# Power_Supply_Alternate.net
KiCad netlist of a schematic drawn in Altium Designer
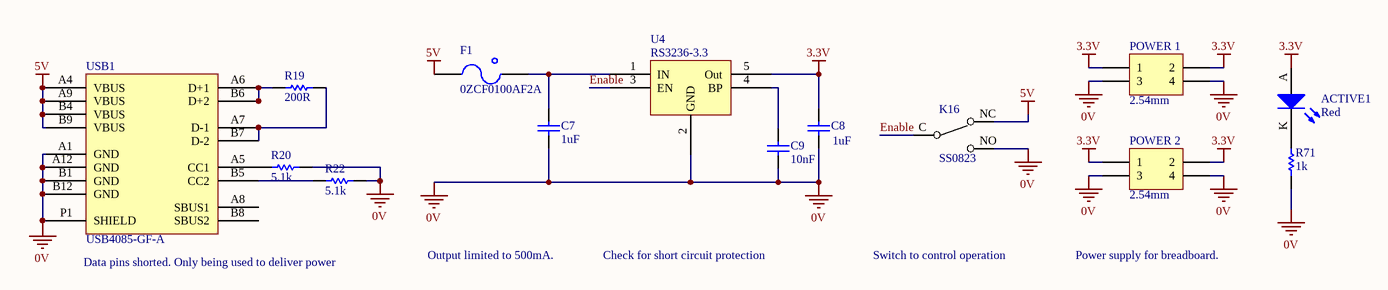
[diagram p0: Power Supply (Alternate).SchDoc]

(export (version "E")
  (design (tool "Eeschema 10.0.6"))
  (components
    (comp (ref "ACTIVE1")
      (value "Red")
      (footprint "0805 LED")
      (description "Red LED Indication - Discrete 1.75V 0805 (2012 Metric)")
      (fields (field (name "PART NUMBER") "SML-210LTT86") (field (name "MANUFACTURER") "ROHM Semiconductor"))
      (libsource (lib "ts_19-standard-library") (part "LED"))
    )
    (comp (ref "C7")
      (value "1uF")
      (footprint "0805")
      (fields
        (field (name "PART NUMBER") "GCM21BR71A105KA37L")
        (field (name "TOLERANCE") "10%")
        (field (name "MANUFACTURER") "muRata")
      )
      (libsource (lib "ts_19-standard-library") (part "Capacitor"))
    )
    (comp (ref "C8")
      (value "1uF")
      (footprint "0805")
      (fields
        (field (name "PART NUMBER") "GCM21BR71A105KA37L")
        (field (name "TOLERANCE") "10%")
        (field (name "MANUFACTURER") "muRata")
      )
      (libsource (lib "ts_19-standard-library") (part "Capacitor"))
    )
    (comp (ref "C9")
      (value "10nF")
      (footprint "0805")
      (fields
        (field (name "PART NUMBER") "GCM21BR71H103KA37L")
        (field (name "TOLERANCE") "10%")
        (field (name "MANUFACTURER") "muRata")
      )
      (libsource (lib "ts_19-standard-library") (part "Capacitor"))
    )
    (comp (ref "F1")
      (value "0ZCF0100AF2A")
      (footprint "2920")
      (description "PTC RESET FUSE 60V 1A 292")
      (fields
        (field (name "MANUFACTURER") "Littelfuse Inc.")
        (field (name "DIGIKEY PART NUMBER") "507-2070-1-ND")
      )
      (libsource (lib "ts_19-standard-library") (part "PTC Fuse"))
    )
    (comp (ref "K16")
      (value "SS0823")
      (footprint "Jaycar 2.54 SPDT Slide")
      (description "SPDT Switch")
      (fields (field (name "MANUFACTURER") "Jaycar"))
      (libsource (lib "ts_19-standard-library") (part "SPDT"))
    )
    (comp (ref "POWER 1")
      (value "2.54mm")
      (footprint "Header 2x2")
      (fields (field (name "PART NUMBER") "Header 2x2") (field (name "CONTACT") "NA"))
      (libsource (lib "ts_19-standard-connectors-IED") (part "Header 2x2"))
    )
    (comp (ref "POWER 2")
      (value "2.54mm")
      (footprint "Header 2x2")
      (fields (field (name "PART NUMBER") "Header 2x2") (field (name "CONTACT") "NA"))
      (libsource (lib "ts_19-standard-connectors-IED") (part "Header 2x2"))
    )
    (comp (ref "R19")
      (value "200R")
      (footprint "0805")
      (fields
        (field (name "MANUFACTURER") "YAGEO")
        (field (name "PART NUMBER") "RC0805FR07200RL")
        (field (name "TOLERANCE") "0.01")
      )
      (libsource (lib "ts_19-standard-library-IED") (part "Resistor"))
    )
    (comp (ref "R20")
      (value "5.1k")
      (footprint "0805")
      (fields
        (field (name "MANUFACTURER") "YAGEO")
        (field (name "PART NUMBER") "RC0805FR075K1L")
        (field (name "TOLERANCE") "0.01")
      )
      (libsource (lib "ts_19-standard-library-IED") (part "Resistor"))
    )
    (comp (ref "R22")
      (value "5.1k")
      (footprint "0805")
      (fields
        (field (name "MANUFACTURER") "YAGEO")
        (field (name "PART NUMBER") "RC0805FR075K1L")
        (field (name "TOLERANCE") "0.01")
      )
      (libsource (lib "ts_19-standard-library-IED") (part "Resistor"))
    )
    (comp (ref "R71")
      (value "1k")
      (footprint "0805")
      (fields
        (field (name "PART NUMBER") "RC0805FR071KL")
        (field (name "MANUFACTURER") "YAGEO")
        (field (name "TOLERANCE") "0.01")
      )
      (libsource (lib "ts_19-standard-library") (part "Resistor"))
    )
    (comp (ref "U4")
      (value "RS3236-3.3")
      (footprint "Runic SOT-23-5")
      (description "Low Power, Low Dropout, 500mA RF LinearRegulators")
      (fields (field (name "MANUFACTURER") "RUNIC"))
      (libsource (lib "ts_19-standard-library") (part "RS3236-3.3"))
    )
    (comp (ref "USB1")
      (value "USB4085-GF-A")
      (footprint "USB4085-GF-A")
      (description "USB - C (Type - C) USB 2.0 Receptacle Connector 16 Position Through Hole, Right Angle")
      (fields (field (name "DIGIKEY PART NUMBER") "2073-USB4085-GF-ACT-ND"))
      (libsource (lib "ts_19-standard-connectors") (part "USB4085-GF-A"))
    )
  )
  (nets
    (net (code "1") (name "/Enable") (class "Default")
      (node (ref "K16") (pin "C") (pinfunction "C_C") (pintype "passive"))
      (node (ref "U4") (pin "3") (pinfunction "EN_3") (pintype "passive"))
    )
    (net (code "2") (name "0V") (class "Default")
      (node (ref "C7") (pin "1") (pinfunction "1_1") (pintype "passive"))
      (node (ref "C8") (pin "1") (pinfunction "1_1") (pintype "passive"))
      (node (ref "C9") (pin "1") (pinfunction "1_1") (pintype "passive"))
      (node (ref "K16") (pin "NO") (pinfunction "NO_NO") (pintype "passive"))
      (node (ref "POWER 1") (pin "3") (pinfunction "3_3") (pintype "passive"))
      (node (ref "POWER 1") (pin "4") (pinfunction "4_4") (pintype "passive"))
      (node (ref "POWER 2") (pin "3") (pinfunction "3_3") (pintype "passive"))
      (node (ref "POWER 2") (pin "4") (pinfunction "4_4") (pintype "passive"))
      (node (ref "R20") (pin "2") (pinfunction "2_2") (pintype "passive"))
      (node (ref "R22") (pin "2") (pinfunction "2_2") (pintype "passive"))
      (node (ref "R71") (pin "1") (pinfunction "1_1") (pintype "passive"))
      (node (ref "U4") (pin "2") (pinfunction "GND_2") (pintype "passive"))
      (node (ref "USB1") (pin "A1") (pinfunction "GND_A1") (pintype "passive"))
      (node (ref "USB1") (pin "A12") (pinfunction "GND_A12") (pintype "passive"))
      (node (ref "USB1") (pin "B1") (pinfunction "GND_B1") (pintype "passive"))
      (node (ref "USB1") (pin "B12") (pinfunction "GND_B12") (pintype "passive"))
      (node (ref "USB1") (pin "P1") (pinfunction "SHIELD_P1") (pintype "passive"))
    )
    (net (code "3") (name "3.3V") (class "Default")
      (node (ref "ACTIVE1") (pin "A") (pinfunction "A_A") (pintype "passive"))
      (node (ref "C8") (pin "2") (pinfunction "2_2") (pintype "passive"))
      (node (ref "POWER 1") (pin "1") (pinfunction "1_1") (pintype "passive"))
      (node (ref "POWER 1") (pin "2") (pinfunction "2_2") (pintype "passive"))
      (node (ref "POWER 2") (pin "1") (pinfunction "1_1") (pintype "passive"))
      (node (ref "POWER 2") (pin "2") (pinfunction "2_2") (pintype "passive"))
      (node (ref "U4") (pin "5") (pinfunction "Out_5") (pintype "passive"))
    )
    (net (code "4") (name "5V") (class "Default")
      (node (ref "F1") (pin "1") (pinfunction "1_1") (pintype "passive"))
      (node (ref "K16") (pin "NC") (pinfunction "NC_NC") (pintype "passive"))
      (node (ref "USB1") (pin "A4") (pinfunction "VBUS_A4") (pintype "passive"))
      (node (ref "USB1") (pin "A9") (pinfunction "VBUS_A9") (pintype "passive"))
      (node (ref "USB1") (pin "B4") (pinfunction "VBUS_B4") (pintype "passive"))
      (node (ref "USB1") (pin "B9") (pinfunction "VBUS_B9") (pintype "passive"))
    )
    (net (code "5") (name "Net-(ACTIVE1-PadK)") (class "Default")
      (node (ref "ACTIVE1") (pin "K") (pinfunction "K_K") (pintype "passive"))
      (node (ref "R71") (pin "2") (pinfunction "2_2") (pintype "passive"))
    )
    (net (code "6") (name "Net-(U4-BP)") (class "Default")
      (node (ref "C9") (pin "2") (pinfunction "2_2") (pintype "passive"))
      (node (ref "U4") (pin "4") (pinfunction "BP_4") (pintype "passive"))
    )
    (net (code "7") (name "Net-(U4-IN)") (class "Default")
      (node (ref "C7") (pin "2") (pinfunction "2_2") (pintype "passive"))
      (node (ref "F1") (pin "2") (pinfunction "2_2") (pintype "passive"))
      (node (ref "U4") (pin "1") (pinfunction "IN_1") (pintype "passive"))
    )
    (net (code "8") (name "Net-(USB1-CC1)") (class "Default")
      (node (ref "R20") (pin "1") (pinfunction "1_1") (pintype "passive"))
      (node (ref "USB1") (pin "A5") (pinfunction "CC1_A5") (pintype "passive"))
    )
    (net (code "9") (name "Net-(USB1-CC2)") (class "Default")
      (node (ref "R22") (pin "1") (pinfunction "1_1") (pintype "passive"))
      (node (ref "USB1") (pin "B5") (pinfunction "CC2_B5") (pintype "passive"))
    )
    (net (code "10") (name "Net-(USB1-D+1)") (class "Default")
      (node (ref "R19") (pin "1") (pinfunction "1_1") (pintype "passive"))
      (node (ref "USB1") (pin "A6") (pinfunction "D+1_A6") (pintype "passive"))
      (node (ref "USB1") (pin "B6") (pinfunction "D+2_B6") (pintype "passive"))
    )
    (net (code "11") (name "Net-(USB1-D-1)") (class "Default")
      (node (ref "R19") (pin "2") (pinfunction "2_2") (pintype "passive"))
      (node (ref "USB1") (pin "A7") (pinfunction "D-1_A7") (pintype "passive"))
      (node (ref "USB1") (pin "B7") (pinfunction "D-2_B7") (pintype "passive"))
    )
    (net (code "12") (name "unconnected-(USB1-SBUS1-PadA8)") (class "Default")
      (node (ref "USB1") (pin "A8") (pinfunction "SBUS1_A8") (pintype "passive"))
    )
    (net (code "13") (name "unconnected-(USB1-SBUS2-PadB8)") (class "Default")
      (node (ref "USB1") (pin "B8") (pinfunction "SBUS2_B8") (pintype "passive"))
    )
  )
)
